# 1000374_1.net
KiCad netlist of a schematic drawn in Altium Designer
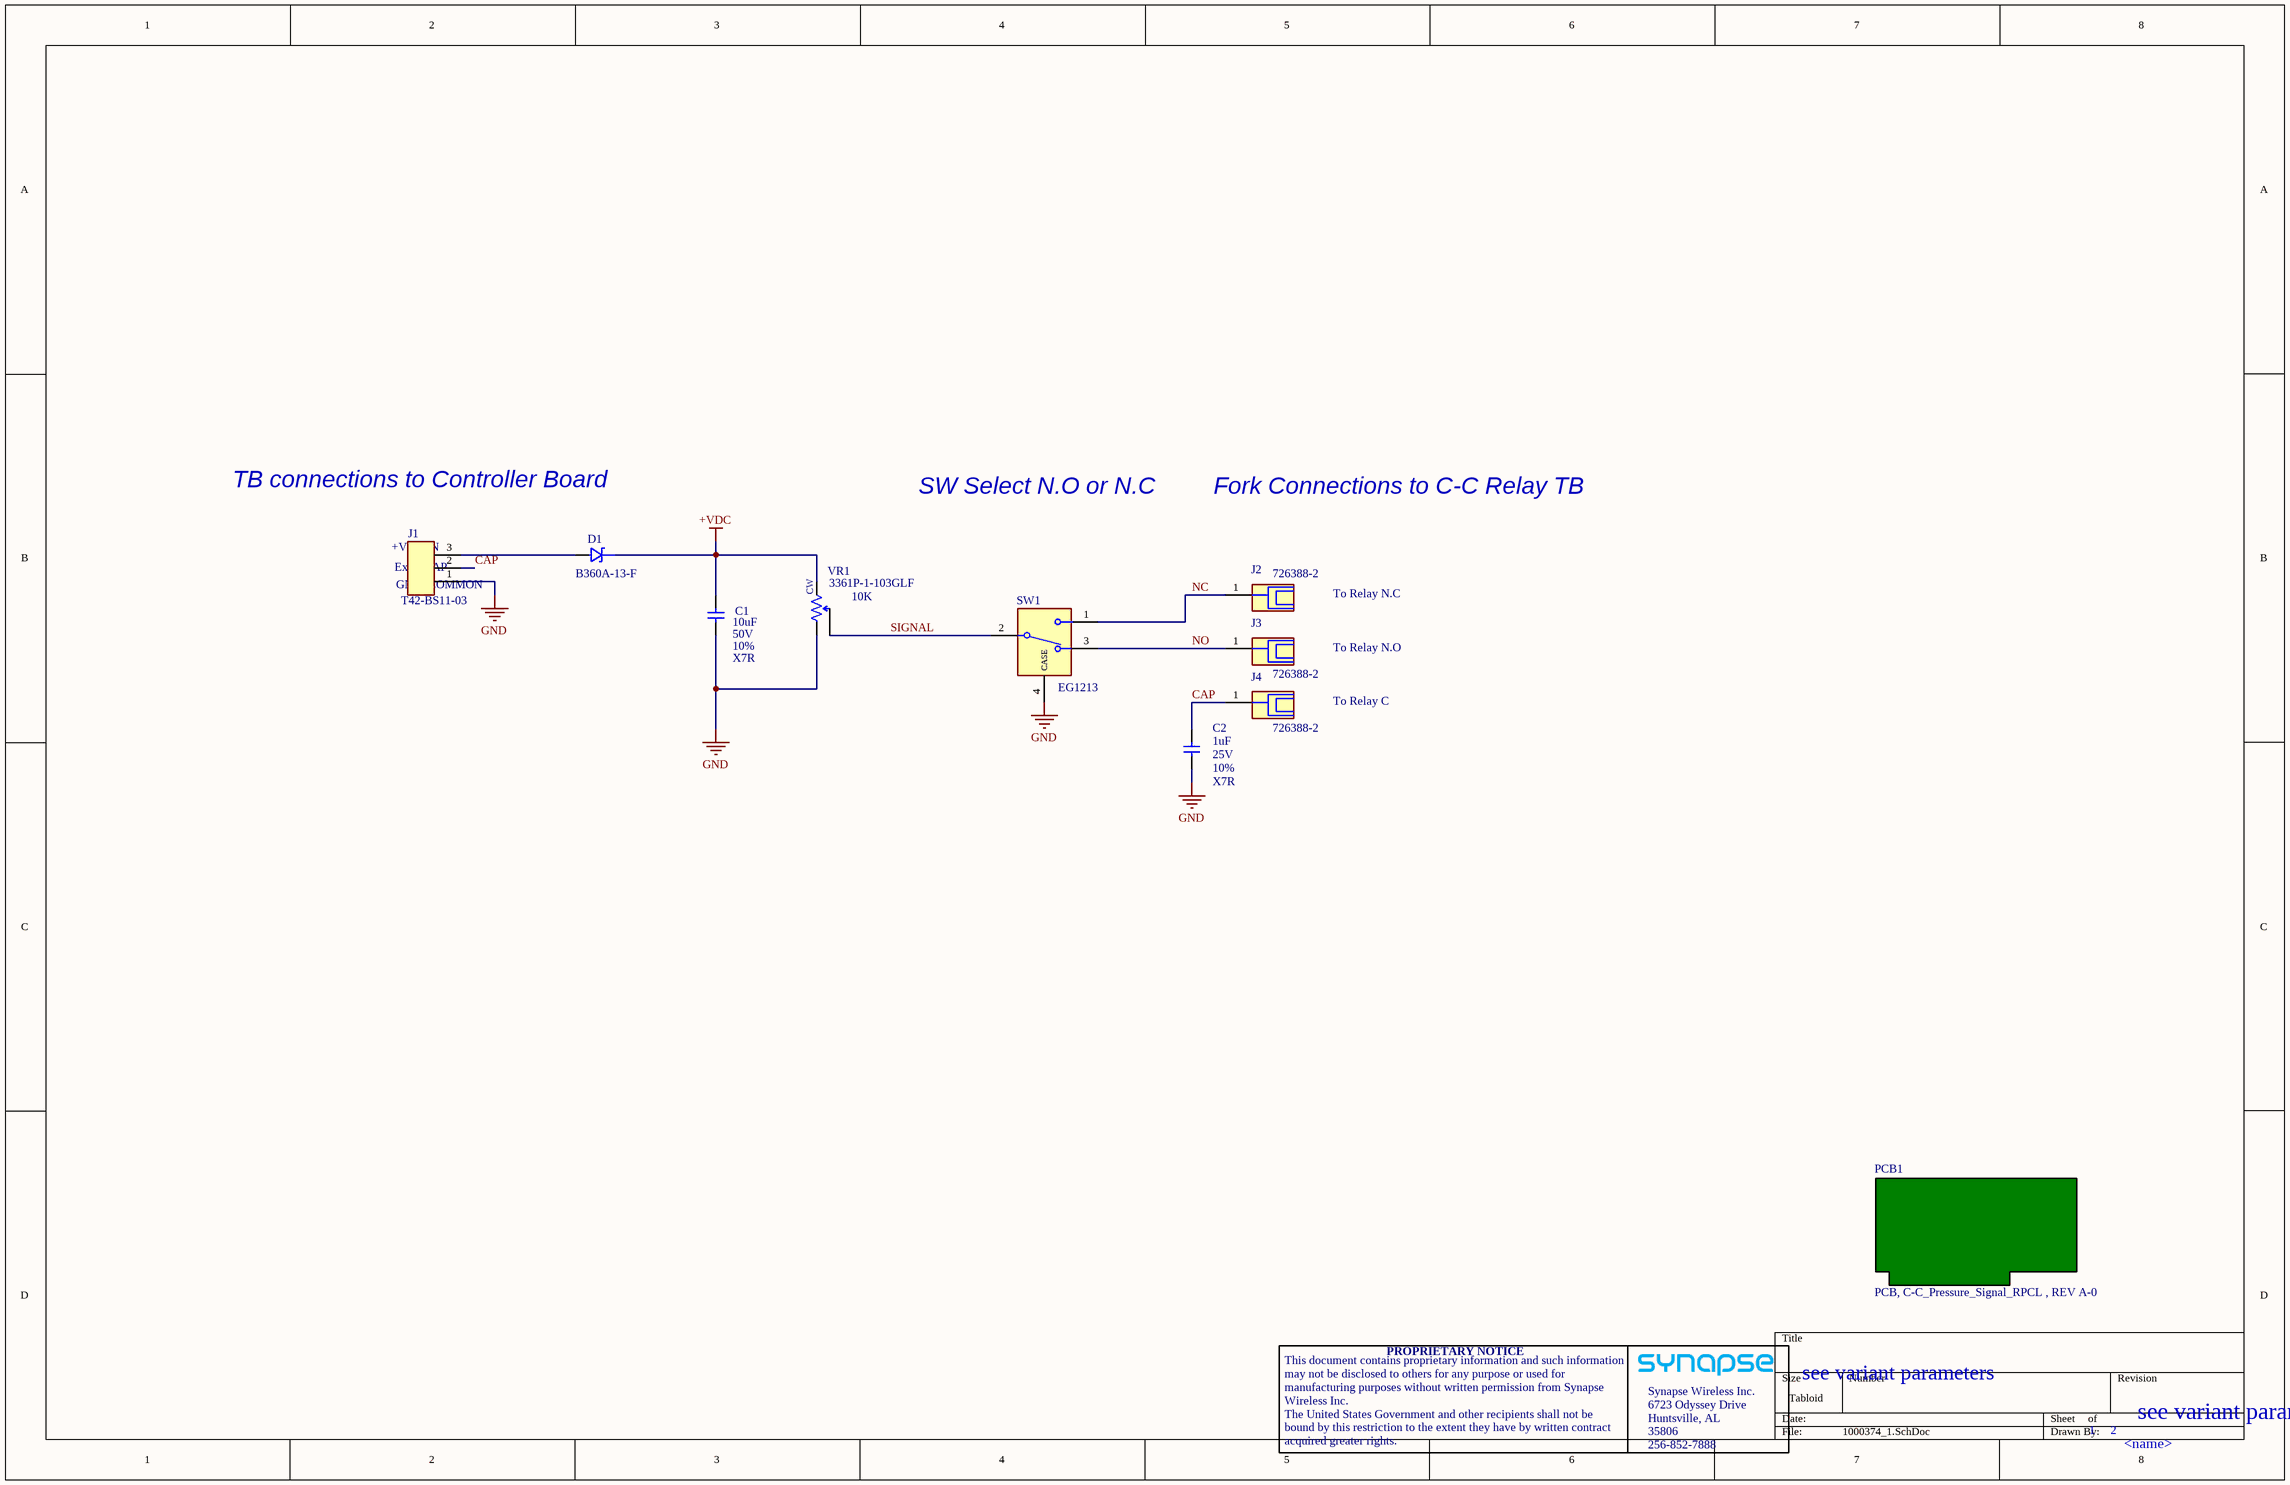
[diagram p0: 1000374_1.SchDoc]

(export (version "E")
  (design (tool "Eeschema 10.0.6"))
  (components
    (comp (ref "C1")
      (value "10uF")
      (footprint "CAPC1210(3225Metric)N")
      (description "Capacitor, ceramic, 10µF, 50V, 10%, X7R, 1210 (3225 Metric), 2.7 mm height, general purpose")
      (fields
        (field (name "MFG") "Murata")
        (field (name "MFG PART NUMBER") "GRM32ER71H106KA12L")
        (field (name "TEMP COEFFICIENT") "X7R")
        (field (name "TOLERANCE") "10%")
        (field (name "VOLTAGE") "50V")
      )
      (libsource (lib "Capacitors") (part "CAP441-A.1"))
    )
    (comp (ref "C2")
      (value "1uF")
      (footprint "CAPC0603(1608Metric)L")
      (description "Capacitor, ceramic, 1uF, 25V, 10%, X7R, 0603 (1608 Metric), 0.9mm height, SMT")
      (fields
        (field (name "PART NUMBER") "CAP294")
        (field (name "MFG") "KEMET")
        (field (name "TEMP COEFFICIENT") "X7R")
        (field (name "TOLERANCE") "10%")
        (field (name "VOLTAGE") "25V")
      )
      (libsource (lib "Capacitors-Trial") (part "CAP"))
    )
    (comp (ref "D1")
      (value "B360A-13-F")
      (footprint "DIODE_DO-214AC (SMA)_5.3X2.8X2.3MM")
      (description "Diode, schottky, 60V, 3A, 700mV forward voltage @ 3A, fast recovery, DO-214AC, 5.6x2.9x2.4mm")
      (fields (field (name "MFG") "Diodes Inc") (field (name "PART NUMBER") "DIO153"))
      (libsource (lib "Diodes") (part "DIO153-A.1"))
    )
    (comp (ref "J1")
      (value "T42-BS11-03")
      (footprint "TE_2-1437667-5-3 POS")
      (description "CONN,BARRIER STRIP, 3POS, 0.325\" PITCH, 14-22AWG,300V,15A,CAPTIVE PLATE,3-WALL,NO COVER")
      (fields (field (name "MFG") "SWITCHLAB INC") (field (name "PART NUMBER") "CON481"))
      (libsource (lib "Connectors") (part "CON481"))
    )
    (comp (ref "J2")
      (value "726388-2")
      (footprint "TE_726388-2_SM")
      (description "Connector, SMT EDGE, QC TAB, SOLDER, for screw fork use, 13.8x6.4x4.75mm")
      (fields (field (name "MFG") "EMERSON") (field (name "MFG PART NUMBER") "142-0771-831"))
      (libsource (lib "1000374") (part "CON???"))
    )
    (comp (ref "J3")
      (value "726388-2")
      (footprint "TE_726388-2_SM")
      (description "Connector, SMT EDGE, QC TAB, SOLDER, for screw fork use, 13.8x6.4x4.75mm")
      (fields (field (name "MFG") "EMERSON") (field (name "MFG PART NUMBER") "142-0771-831"))
      (libsource (lib "1000374") (part "CON???"))
    )
    (comp (ref "J4")
      (value "726388-2")
      (footprint "TE_726388-2_SM")
      (description "Connector, SMT EDGE, QC TAB, SOLDER, for screw fork use, 13.8x6.4x4.75mm")
      (fields (field (name "MFG") "EMERSON") (field (name "MFG PART NUMBER") "142-0771-831"))
      (libsource (lib "1000374") (part "CON???"))
    )
    (comp (ref "PCB1")
      (value "PCB, C-C_Pressure_Signal_RPCL , REV A-0")
      (description "Bare PCB")
      (fields (field (name "PART NUMBER") "1000374") (field (name "MFG") "SYNAPSE"))
      (libsource (lib "Z_Miscellaneous") (part "PCB2-A.1"))
    )
    (comp (ref "SW1")
      (value "EG1213")
      (footprint "SWITCH_PTH_E-SWITCH_EG1213")
      (description "Switch, slide, SPDT, standard, 200mA, 30V, RA, PTH, 10x8.8x5mm")
      (fields (field (name "MFG") "E-Switch") (field (name "PART NUMBER") "SW044"))
      (libsource (lib "Switches") (part "SW044-A.1"))
    )
    (comp (ref "VR1")
      (value "3361P-1-103GLF")
      (footprint "TRIM_3361P-1-103GLF")
      (description "Potentiometer, trimmer, cermet, 10K, 0.5W, top adjust, 1.0 turns, 10%, 100ppm, SM, 7.04mmx6.7mm")
      (fields
        (field (name "MFG") "BOURNS")
        (field (name "PART NUMBER") "POTEN002")
        (field (name "ALTIUM_VALUE") "10K")
      )
      (libsource (lib "1000374") (part "POTEN002"))
    )
  )
  (nets
    (net (code "1") (name "+VDC") (class "Default")
      (node (ref "C1") (pin "2") (pinfunction "2_2") (pintype "passive"))
      (node (ref "D1") (pin "K") (pinfunction "K_K") (pintype "passive"))
      (node (ref "VR1") (pin "3") (pinfunction "3_3") (pintype "passive"))
    )
    (net (code "2") (name "/CAP") (class "Default")
      (node (ref "C2") (pin "1") (pinfunction "1_1") (pintype "passive"))
      (node (ref "J1") (pin "2") (pinfunction "2_2") (pintype "passive"))
      (node (ref "J4") (pin "1") (pinfunction "GND_1") (pintype "passive"))
    )
    (net (code "3") (name "/NC") (class "Default")
      (node (ref "J2") (pin "1") (pinfunction "GND_1") (pintype "passive"))
      (node (ref "SW1") (pin "1") (pinfunction "1_1") (pintype "passive"))
    )
    (net (code "4") (name "/NO") (class "Default")
      (node (ref "J3") (pin "1") (pinfunction "GND_1") (pintype "passive"))
      (node (ref "SW1") (pin "3") (pinfunction "3_3") (pintype "passive"))
    )
    (net (code "5") (name "/SIGNAL") (class "Default")
      (node (ref "SW1") (pin "2") (pinfunction "2_2") (pintype "passive"))
      (node (ref "VR1") (pin "2") (pinfunction "2_2") (pintype "passive"))
    )
    (net (code "6") (name "GND") (class "Default")
      (node (ref "C1") (pin "1") (pinfunction "1_1") (pintype "passive"))
      (node (ref "C2") (pin "2") (pinfunction "2_2") (pintype "passive"))
      (node (ref "J1") (pin "1") (pinfunction "1_1") (pintype "passive"))
      (node (ref "SW1") (pin "4") (pinfunction "CASE_4") (pintype "passive"))
      (node (ref "VR1") (pin "1") (pinfunction "1_1") (pintype "passive"))
    )
    (net (code "7") (name "Net-(D1-PadA)") (class "Default")
      (node (ref "D1") (pin "A") (pinfunction "A_A") (pintype "passive"))
      (node (ref "J1") (pin "3") (pinfunction "3_3") (pintype "passive"))
    )
  )
)
